# Sheet1.net
KiCad netlist of a schematic drawn in Altium Designer
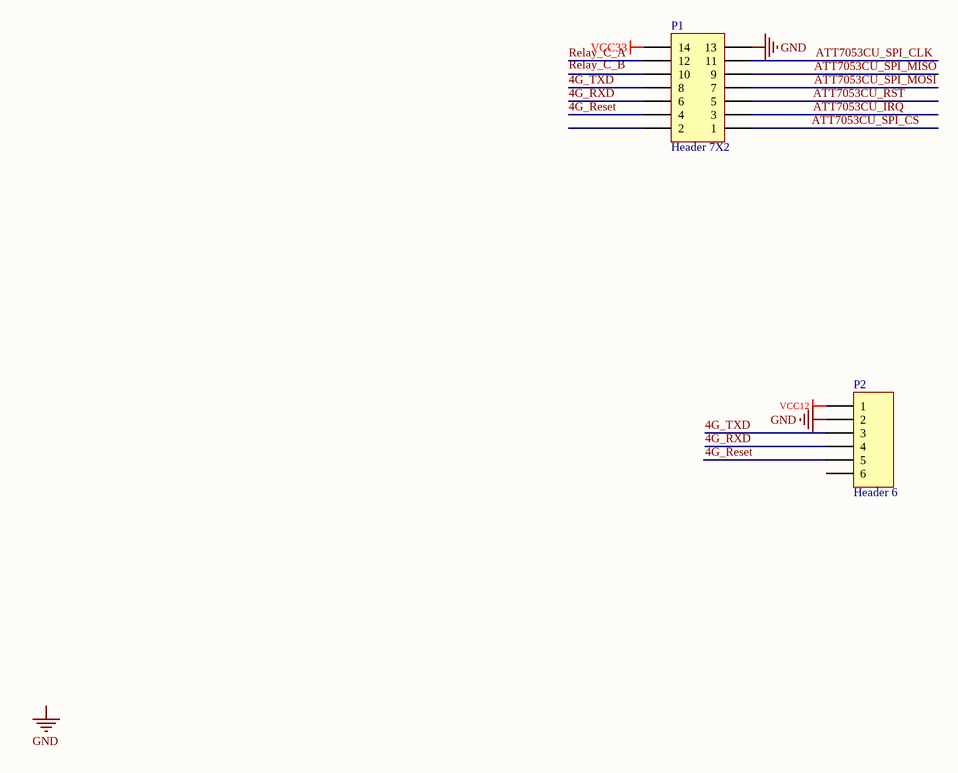
[diagram p0: Sheet1.SchDoc]

(export (version "E")
  (design (tool "Eeschema 10.0.6"))
  (components
    (comp (ref "P1")
      (value "Header 7X2")
      (footprint "HDR2X7")
      (description "Header, 7-Pin, Dual row")
      (fields (field (name "PUBLISHER") "Altium Limited"))
      (libsource (lib "Miscellaneous Connectors") (part "Header 7X2"))
    )
    (comp (ref "P2")
      (value "Header 6")
      (footprint "HDR1X6")
      (description "Header, 6-Pin")
      (fields (field (name "PUBLISHER") "Altium Limited"))
      (libsource (lib "Miscellaneous Connectors") (part "Header 6"))
    )
  )
  (nets
    (net (code "1") (name "/4G_RXD") (class "Default")
      (node (ref "P1") (pin "6") (pinfunction "6_6") (pintype "passive"))
      (node (ref "P2") (pin "4") (pinfunction "4_4") (pintype "passive"))
    )
    (net (code "2") (name "/4G_Reset") (class "Default")
      (node (ref "P1") (pin "4") (pinfunction "4_4") (pintype "passive"))
      (node (ref "P2") (pin "5") (pinfunction "5_5") (pintype "passive"))
    )
    (net (code "3") (name "/4G_TXD") (class "Default")
      (node (ref "P1") (pin "8") (pinfunction "8_8") (pintype "passive"))
      (node (ref "P2") (pin "3") (pinfunction "3_3") (pintype "passive"))
    )
    (net (code "4") (name "/ATT7053CU_IRQ") (class "Default")
      (node (ref "P1") (pin "3") (pinfunction "3_3") (pintype "passive"))
    )
    (net (code "5") (name "/ATT7053CU_RST") (class "Default")
      (node (ref "P1") (pin "5") (pinfunction "5_5") (pintype "passive"))
    )
    (net (code "6") (name "/ATT7053CU_SPI_CLK") (class "Default")
      (node (ref "P1") (pin "11") (pinfunction "11_11") (pintype "passive"))
    )
    (net (code "7") (name "/ATT7053CU_SPI_CS") (class "Default")
      (node (ref "P1") (pin "1") (pinfunction "1_1") (pintype "passive"))
    )
    (net (code "8") (name "/ATT7053CU_SPI_MISO") (class "Default")
      (node (ref "P1") (pin "9") (pinfunction "9_9") (pintype "passive"))
    )
    (net (code "9") (name "/ATT7053CU_SPI_MOSI") (class "Default")
      (node (ref "P1") (pin "7") (pinfunction "7_7") (pintype "passive"))
    )
    (net (code "10") (name "/Relay_C_A") (class "Default")
      (node (ref "P1") (pin "12") (pinfunction "12_12") (pintype "passive"))
    )
    (net (code "12") (name "GND") (class "Default")
      (node (ref "P1") (pin "13") (pinfunction "13_13") (pintype "passive"))
      (node (ref "P2") (pin "2") (pinfunction "2_2") (pintype "passive"))
    )
    (net (code "13") (name "VCC12") (class "Default")
      (node (ref "P2") (pin "1") (pinfunction "1_1") (pintype "passive"))
    )
    (net (code "14") (name "VCC33") (class "Default")
      (node (ref "P1") (pin "14") (pinfunction "14_14") (pintype "passive"))
    )
    (net (code "15") (name "unconnected-(P1-Pad2)") (class "Default")
      (node (ref "P1") (pin "2") (pinfunction "2_2") (pintype "passive"))
    )
    (net (code "16") (name "unconnected-(P1-Pad10)") (class "Default")
      (node (ref "P1") (pin "10") (pinfunction "10_10") (pintype "passive"))
    )
    (net (code "17") (name "unconnected-(P2-Pad6)") (class "Default")
      (node (ref "P2") (pin "6") (pinfunction "6_6") (pintype "passive"))
    )
  )
)
